# led_pack32.net
KiCad netlist of a schematic drawn in Altium Designer
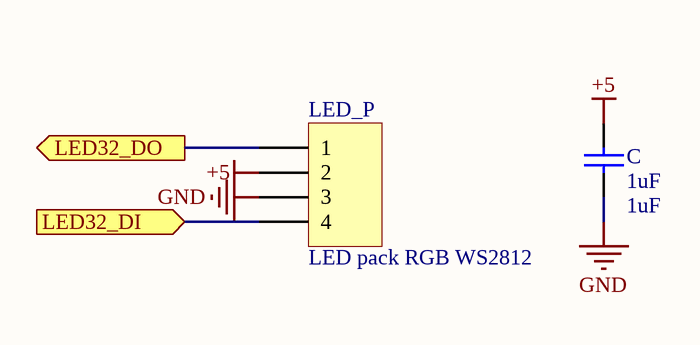
[diagram p0: led_pack32.SchDoc]

(export (version "E")
  (design (tool "Eeschema 10.0.6"))
  (components
    (comp (ref "C")
      (value "1uF")
      (footprint "0603C")
      (description "CAP SMD 0603")
      (fields (field (name "ALTIUM_VALUE") "1uF") (field (name "PUBLISHER") "Altium Limited"))
      (libsource (lib "Miscellaneous Devices") (part "Cap"))
    )
    (comp (ref "LED_P")
      (value "LED pack RGB WS2812")
      (footprint "PACK32-2121")
      (description "8RGB LED pack")
      (fields (field (name "PUBLISHER") "Altium Limited"))
      (libsource (lib "Altium") (part "Header 4"))
    )
  )
  (nets
    (net (code "1") (name "+5") (class "Default")
      (node (ref "C") (pin "2") (pinfunction "2_2") (pintype "passive"))
      (node (ref "LED_P") (pin "2") (pinfunction "2_2") (pintype "passive"))
    )
    (net (code "2") (name "/LED32_DI") (class "Default")
      (node (ref "LED_P") (pin "4") (pinfunction "4_4") (pintype "passive"))
    )
    (net (code "3") (name "/LED32_DO") (class "Default")
      (node (ref "LED_P") (pin "1") (pinfunction "1_1") (pintype "passive"))
    )
    (net (code "4") (name "GND") (class "Default")
      (node (ref "C") (pin "1") (pinfunction "1_1") (pintype "passive"))
      (node (ref "LED_P") (pin "3") (pinfunction "3_3") (pintype "passive"))
    )
  )
)
